# Phase_2.net
KiCad netlist of a schematic drawn in Altium Designer
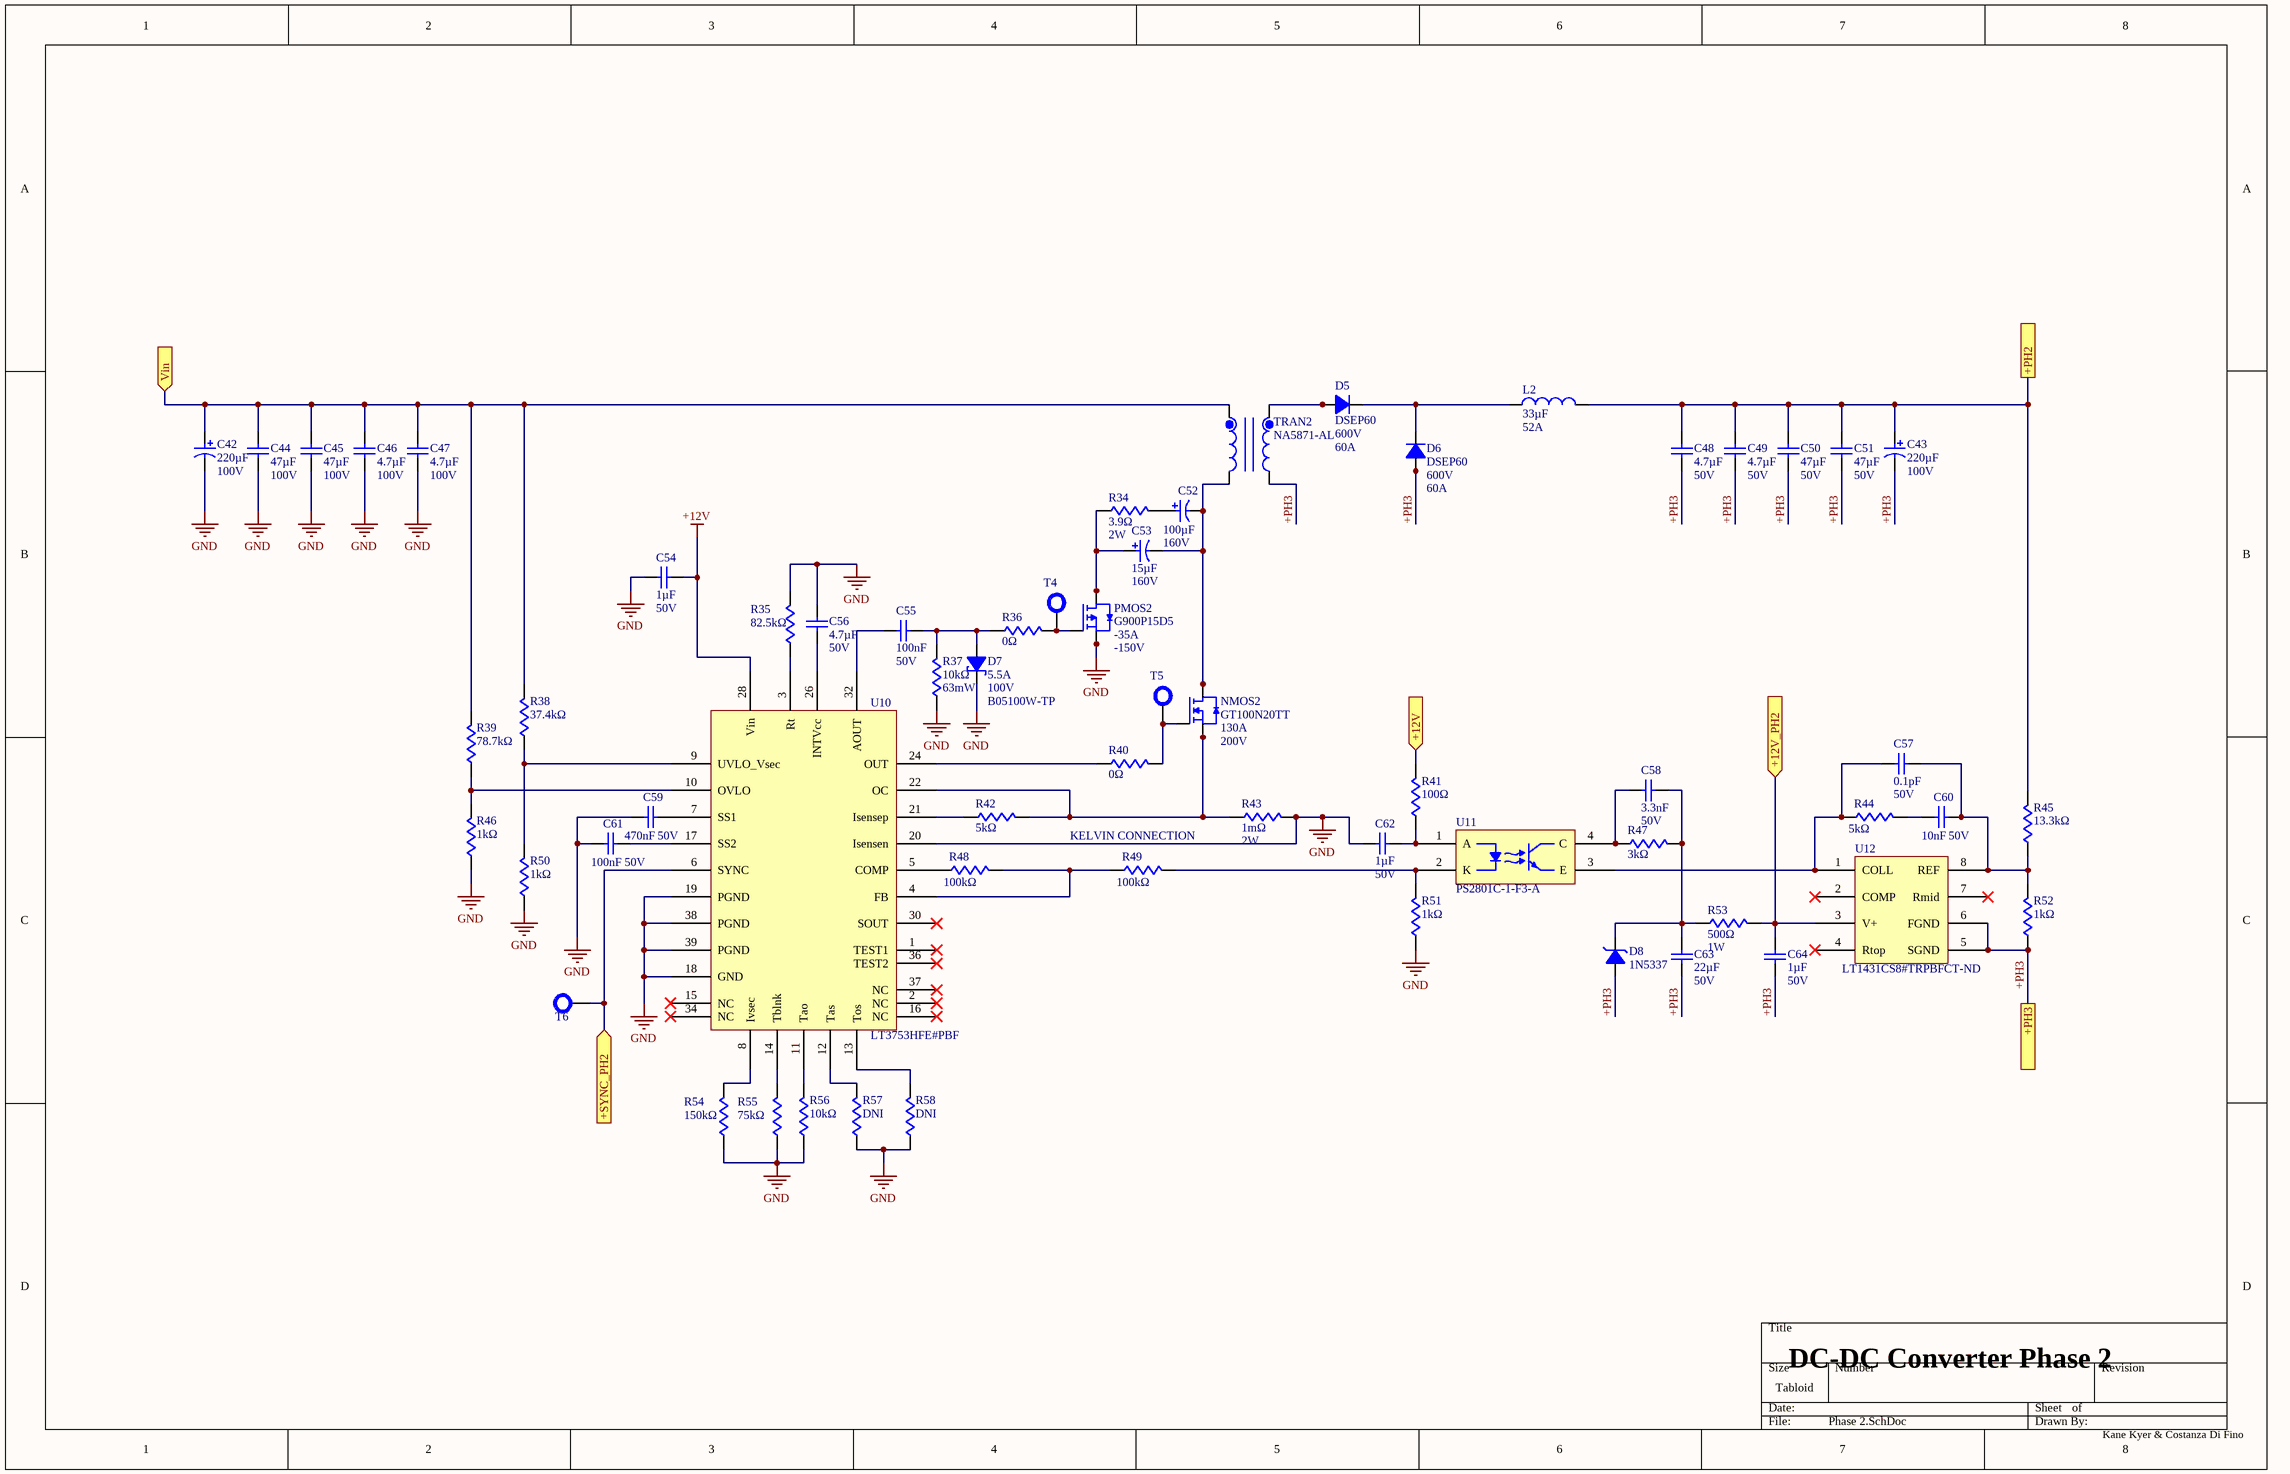
[diagram p0: Phase 2.SchDoc]

(export (version "E")
  (design (tool "Eeschema 10.0.6"))
  (components
    (comp (ref "C42")
      (value "220µF")
      (footprint "C_AEC")
      (description "Radial Can - SMD ALUMINUM ELECTROLYTIC CAPACITOR AFK 100V 220muF ±20% 0.709Dia 18.00mm")
      (fields
        (field (name "MANUFACTURER") "Cornell Dubilier")
        (field (name "MANUFACTURER PART NUMBER") "AFK227M2AR44T-F")
        (field (name "VOLTAGE RATING") "100V")
      )
      (libsource (lib "library") (part "AFK227M2AR44T-F"))
    )
    (comp (ref "C43")
      (value "220µF")
      (footprint "C_AEC")
      (description "Radial Can - SMD ALUMINUM ELECTROLYTIC CAPACITOR AFK 100V 220muF ±20% 0.709Dia 18.00mm")
      (fields
        (field (name "MANUFACTURER") "Cornell Dubilier")
        (field (name "MANUFACTURER PART NUMBER") "AFK227M2AR44T-F")
        (field (name "VOLTAGE RATING") "100V")
      )
      (libsource (lib "library") (part "AFK227M2AR44T-F"))
    )
    (comp (ref "C44")
      (value "47µF")
      (footprint "C_CAA573")
      (description "Multilayer Ceramic Chip Capacitors, Capacitance=47μF, LxWxT: 6.0x7.5x6.4mm")
      (fields
        (field (name "MANUFACTURER") "TDK")
        (field (name "MANUFACTURER PART NUMBER") "CAA573X7S2A476M640LH")
        (field (name "VOLTAGE RATING") "100V")
      )
      (libsource (lib "library") (part "CAA573X7S2A476M640LH"))
    )
    (comp (ref "C45")
      (value "47µF")
      (footprint "C_CAA573")
      (description "Multilayer Ceramic Chip Capacitors, Capacitance=47μF, LxWxT: 6.0x7.5x6.4mm")
      (fields
        (field (name "MANUFACTURER") "TDK")
        (field (name "MANUFACTURER PART NUMBER") "CAA573X7S2A476M640LH")
        (field (name "VOLTAGE RATING") "100V")
      )
      (libsource (lib "library") (part "CAA573X7S2A476M640LH"))
    )
    (comp (ref "C46")
      (value "4.7µF")
      (footprint "C_1210")
      (fields
        (field (name "MANUFACTURER") "Cal-Chip Electronics")
        (field (name "MANUFACTURER PART NUMBER") "GMC32X7S475K100NT")
        (field (name "VOLTAGE RATING (DC)") "100V")
      )
      (libsource (lib "library") (part "GMC32X7S475K100NT"))
    )
    (comp (ref "C47")
      (value "4.7µF")
      (footprint "C_1210")
      (fields
        (field (name "MANUFACTURER") "Cal-Chip Electronics")
        (field (name "MANUFACTURER PART NUMBER") "GMC32X7S475K100NT")
        (field (name "VOLTAGE RATING (DC)") "100V")
      )
      (libsource (lib "library") (part "GMC32X7S475K100NT"))
    )
    (comp (ref "C48")
      (value "4.7µF")
      (footprint "C_1206")
      (fields
        (field (name "MANUFACTURER") "Cal-Chip Electronics")
        (field (name "MANUFACTURER PART NUMBER") "GMC31X7R475K50NT")
        (field (name "VOLTAGE RATING (DC)") "50V")
      )
      (libsource (lib "library") (part "GMC31X7R475K50NT"))
    )
    (comp (ref "C49")
      (value "4.7µF")
      (footprint "C_1206")
      (fields
        (field (name "MANUFACTURER") "Cal-Chip Electronics")
        (field (name "MANUFACTURER PART NUMBER") "GMC31X7R475K50NT")
        (field (name "VOLTAGE RATING (DC)") "50V")
      )
      (libsource (lib "library") (part "GMC31X7R475K50NT"))
    )
    (comp (ref "C50")
      (value "47µF")
      (footprint "C_CKG57N")
      (fields
        (field (name "MANUFACTURER") "TDK")
        (field (name "MANUFACTURER PART NUMBER") "CKG57NX7R1H476M500JJ")
        (field (name "VOLTAGE RATING (DC)") "50V")
      )
      (libsource (lib "library") (part "CKG57NX7R1H476M500JJ"))
    )
    (comp (ref "C51")
      (value "47µF")
      (footprint "C_CKG57N")
      (fields
        (field (name "MANUFACTURER") "TDK")
        (field (name "MANUFACTURER PART NUMBER") "CKG57NX7R1H476M500JJ")
        (field (name "VOLTAGE RATING (DC)") "50V")
      )
      (libsource (lib "library") (part "CKG57NX7R1H476M500JJ"))
    )
    (comp (ref "C52")
      (value "100µF")
      (footprint "UUJ2C101MNJ1MS")
      (description "Aluminum Electrolytic Capacitors 100 F 160 V Radial, SMD 5000 Hrs 105C")
      (fields
        (field (name "MANUFACTURER") "Nichicon")
        (field (name "MANUFACTURER PART NUMBER") "UUJ2C101MNJ1MS")
        (field (name "VOLTAGE RATING (DC)") "160V")
      )
      (libsource (lib "library") (part "UUJ2C101MNJ1MS"))
    )
    (comp (ref "C53")
      (value "15µF")
      (footprint "ULT2C150MNL1GS")
      (description "Radial Can - SMD ALUMINUM ELECTROLYTIC CAPACITOR ULT 160V 15muF ±20% 0.315Dia 8.00mm")
      (fields
        (field (name "MANUFACTURER") "Nichicon")
        (field (name "MANUFACTURER PART NUMBER") "ULT2C150MNL1GS")
        (field (name "VOLTAGE") "160V")
      )
      (libsource (lib "library") (part "ULT2C150MNL1GS"))
    )
    (comp (ref "C54")
      (value "1µF")
      (footprint "C_0805")
      (description "50V 1uF X7R ±10% 0805 Multilayer Ceramic Capacitors MLCC - SMD/SMT ROHS")
      (fields
        (field (name "MANUFACTURER") "Samsung Electro-Mechanics")
        (field (name "MANUFACTURER PART NUMBER") "CL21B105KBFNNNE")
        (field (name "VOLTAGE") "50V")
      )
      (libsource (lib "library") (part "CL21B105KBFNNNE"))
    )
    (comp (ref "C55")
      (value "100nF")
      (footprint "C_0603")
      (description "50V 100nF X7R ±10% 0603 Multilayer Ceramic Capacitors MLCC - SMD/SMT ROHS")
      (fields
        (field (name "MANUFACTURER") "KEMET")
        (field (name "MANUFACTURER PART NUMBER") "C0603C104K5RACTU")
        (field (name "VOLTAGE RATING") "50V")
      )
      (libsource (lib "library") (part "C0603C104K5RACTU"))
    )
    (comp (ref "C56")
      (value "4.7µF")
      (footprint "C_1206")
      (fields
        (field (name "MANUFACTURER") "Cal-Chip Electronics")
        (field (name "MANUFACTURER PART NUMBER") "GMC31X7R475K50NT")
        (field (name "VOLTAGE RATING (DC)") "50V")
      )
      (libsource (lib "library") (part "GMC31X7R475K50NT"))
    )
    (comp (ref "C57")
      (value "0.1pF")
      (footprint "C_0402")
      (description "Multilayer Ceramic Capacitor, 0.1 pF, 50 V, ± 0.05pF, C0G (NP0), 0402 [1005 Metric]")
      (fields
        (field (name "MANUFACTURER") "Murata")
        (field (name "MANUFACTURER PART NUMBER") "GJM1555C1HR10WB01D")
        (field (name "VOLTAGE RATING") "50V")
      )
      (libsource (lib "library") (part "GJM1555C1HR10WB01D"))
    )
    (comp (ref "C58")
      (value "3.3nF")
      (footprint "C_0603")
      (description "50V 3.3nF C0G ±1% 0603 Multilayer Ceramic Capacitors MLCC - SMD/SMT ROHS")
      (fields
        (field (name "MANUFACTURER") "Murata")
        (field (name "MANUFACTURER PART NUMBER") "GCM1885C1H332FA16D")
        (field (name "VOLTAGE RATING") "50V")
      )
      (libsource (lib "library") (part "GCM1885C1H332FA16D"))
    )
    (comp (ref "C59")
      (value "470nF")
      (footprint "C_0402")
      (description "50V 470nF X5R ±10% 0402 Multilayer Ceramic Capacitors MLCC - SMD/SMT ROHS")
      (fields
        (field (name "MANUFACTURER") "Murata")
        (field (name "MANUFACTURER PART NUMBER") "GRM155R61H474KE11D")
        (field (name "VOLTAGE RATING") "50V")
      )
      (libsource (lib "library") (part "GRM155R61H474KE11D"))
    )
    (comp (ref "C60")
      (value "10nF")
      (footprint "C_0603")
      (description "Capacitor, Multilayer, Ceramic, 50V, 10%, X7R, 15% Tc, 0.01Uf, Surface Mount, 0603")
      (fields
        (field (name "MANUFACTURER") "KEMET")
        (field (name "MANUFACTURER PART NUMBER") "C0603C103K5RACTU")
        (field (name "VOLTAGE RATING") "50V")
      )
      (libsource (lib "library") (part "C0603C103K5RACTU"))
    )
    (comp (ref "C61")
      (value "100nF")
      (footprint "C_0603")
      (description "50V 100nF X7R ±10% 0603 Multilayer Ceramic Capacitors MLCC - SMD/SMT ROHS")
      (fields
        (field (name "MANUFACTURER") "KEMET")
        (field (name "MANUFACTURER PART NUMBER") "C0603C104K5RACTU")
        (field (name "VOLTAGE RATING") "50V")
      )
      (libsource (lib "library") (part "C0603C104K5RACTU"))
    )
    (comp (ref "C62")
      (value "1µF")
      (footprint "C_0805")
      (description "50V 1uF X7R ±10% 0805 Multilayer Ceramic Capacitors MLCC - SMD/SMT ROHS")
      (fields
        (field (name "MANUFACTURER") "Samsung Electro-Mechanics")
        (field (name "MANUFACTURER PART NUMBER") "CL21B105KBFNNNE")
        (field (name "VOLTAGE") "50V")
      )
      (libsource (lib "library") (part "CL21B105KBFNNNE"))
    )
    (comp (ref "C63")
      (value "22µF")
      (footprint "C_2220")
      (fields
        (field (name "MANUFACTURER") "Cal-Chip Electronics")
        (field (name "MANUFACTURER PART NUMBER") "GMC55X7R226M50NT")
        (field (name "VOLTAGE RATING (DC)") "50V")
      )
      (libsource (lib "library") (part "GMC55X7R226M50NT"))
    )
    (comp (ref "C64")
      (value "1µF")
      (footprint "C_0805")
      (description "50V 1uF X7R ±10% 0805 Multilayer Ceramic Capacitors MLCC - SMD/SMT ROHS")
      (fields
        (field (name "MANUFACTURER") "Samsung Electro-Mechanics")
        (field (name "MANUFACTURER PART NUMBER") "CL21B105KBFNNNE")
        (field (name "VOLTAGE") "50V")
      )
      (libsource (lib "library") (part "CL21B105KBFNNNE"))
    )
    (comp (ref "D5")
      (value "DSEP60")
      (footprint "D_DSEP60")
      (description "Power Diode Discretes-FRED TO-")
      (fields
        (field (name "MANUFACTURER") "IXYS")
        (field (name "MANUFACTURER PART NUMBER") "DSEP60-06AZ-TRL")
        (field (name "VR") "600V")
        (field (name "IO") "60A")
      )
      (libsource (lib "library") (part "DSEP60-06AZ-TRL"))
    )
    (comp (ref "D6")
      (value "DSEP60")
      (footprint "D_DSEP60")
      (description "Power Diode Discretes-FRED TO-")
      (fields
        (field (name "MANUFACTURER") "IXYS")
        (field (name "MANUFACTURER PART NUMBER") "DSEP60-06AZ-TRL")
        (field (name "VR") "600V")
        (field (name "IO") "60A")
      )
      (libsource (lib "library") (part "DSEP60-06AZ-TRL"))
    )
    (comp (ref "D7")
      (value "B05100W-TP")
      (footprint "D_B05100W")
      (description "Rectifier Diode, Schottky, 1 Phase, 1 Element, 0.5A, 100V V(RRM), Silicon")
      (fields
        (field (name "MANUFACTURER") "MCC")
        (field (name "MAX FORWARD SURGE CURRENT (IFSM)") "5.5A")
        (field (name "MIN BREAKDOWN VOLTAGE") "100V")
        (field (name "MANUFACTURER PART NUMBER") "B05100W-TP")
      )
      (libsource (lib "library") (part "B05100W-TP"))
    )
    (comp (ref "D8")
      (value "1N5337BRLG")
      (footprint "D_1N5337")
      (description "Zener Diode Single 4.7V 5% 2Ohm 5000mW 2-Pin Case 017AA-01 T/R / DIODE ZENER 4.7V 5W AXIAL")
      (fields
        (field (name "MANUFACTURER") "onsemi")
        (field (name "TOLERANCE") "5%")
        (field (name "SUPPLIER PART NUMBER") "1N5337")
      )
      (libsource (lib "library") (part "1N5337BRLG"))
    )
    (comp (ref "L2")
      (value "33µF")
      (footprint "CPEX4141L-330MC")
      (description "Fixed Ind 33UH 52A 1.88 Mohm Th")
      (fields
        (field (name "MANUFACTURER") "Codaca")
        (field (name "MANUFACTURER PART NUMBER") "CPEX4141L-330MC")
        (field (name "IRMS") "52A")
      )
      (libsource (lib "library") (part "CPEX4141L-330MC"))
    )
    (comp (ref "NMOS2")
      (value "GT100N20TT")
      (footprint "GT100N20TT")
      (description "Mosfet N-ch 200V 130A 280W Tolt")
      (fields
        (field (name "MANUFACTURER") "GoFord")
        (field (name "MANUFACTURER PART NUMBER") "GT100N20TT")
        (field (name "ID") "130A")
        (field (name "VDS") "200V")
      )
      (libsource (lib "library") (part "GT100N20TT"))
    )
    (comp (ref "PMOS2")
      (value "G900P15D5")
      (footprint "G900P15")
      (description "P-150V, -60A, RD(max) Less Than 80mOhm at -10V, VTH -1V to -4V, DFN5x6-8L")
      (fields
        (field (name "MANUFACTURER") "GoFord")
        (field (name "MANUFACTURER PART NUMBER") "G900P15D5")
        (field (name "ID") "-35A")
        (field (name "VDS") "-150V")
      )
      (libsource (lib "library") (part "G900P15D5"))
    )
    (comp (ref "R34")
      (value "3.9Ω")
      (footprint "R_SM2W")
      (description "SM Series 3.9 Ohm ±5 % 2 W ±200 ppm/°C Surface Mount Wirewound Resistor")
      (fields
        (field (name "MANUFACTURER") "TE Connectivity")
        (field (name "MANUFACTURER PART NUMBER") "SMW23R9JT")
        (field (name "POWER RATING") "2W")
      )
      (libsource (lib "library") (part "SMW23R9JT"))
    )
    (comp (ref "R35")
      (value "82.5kΩ")
      (footprint "R_0805")
      (description "Res Thick Film 0805 82.5K Ohm 1% 1/8W ±100ppm/°C Molded SMD SMD Paper T/R")
      (fields
        (field (name "MANUFACTURER") "Stackpole Electronics")
        (field (name "MANUFACTURER PART NUMBER") "RMCF0805FT82K5")
      )
      (libsource (lib "library") (part "RMCF0805FT82K5"))
    )
    (comp (ref "R36")
      (value "0Ω")
      (footprint "R_0805")
      (description "Zero Ohm Resistor, Jumper, 0805 [2012 Metric], Thick Film, 125 mW, 2.5 A, Surface Mount Device")
      (fields
        (field (name "MANUFACTURER") "Vishay")
        (field (name "MANUFACTURER PART NUMBER") "CRCW08050000Z0EA")
      )
      (libsource (lib "library") (part "CRCW08050000Z0EA"))
    )
    (comp (ref "R37")
      (value "10kΩ")
      (footprint "R_0402")
      (description "Fixed Resistor, Metal Glaze/thick Film, 0.0625W, 10000ohm, 50V, 1% +/-Tol, Surface Mount, 0402")
      (fields
        (field (name "MANUFACTURER") "Cal-Chip Electronics")
        (field (name "MANUFACTURER PART NUMBER") "RM04F1002CT")
        (field (name "POWER RATING") "63mW")
      )
      (libsource (lib "library") (part "RM04F1002CT"))
    )
    (comp (ref "R38")
      (value "37.4kΩ")
      (footprint "R_0603")
      (description "100mW Thick Film Resistors 75V ±100ppm/℃ ±1% 37.4kΩ 0603 Chip Resistor - Surface Mount ROHS")
      (fields
        (field (name "MANUFACTURER") "Yageo Group")
        (field (name "MANUFACTURER PART NUMBER") "RC0603FR-0737K4L")
      )
      (libsource (lib "library") (part "RC0603FR-0737K4L"))
    )
    (comp (ref "R39")
      (value "78.7kΩ")
      (footprint "R_0603")
      (description "Res Thick Film 0603 78.7K Ohm 1% 0.1W(1/10W) ±100ppm/C Pad SMD T/R")
      (fields
        (field (name "MANUFACTURER") "Yageo Group")
        (field (name "MANUFACTURER PART NUMBER") "RC0603FR-0778K7L")
      )
      (libsource (lib "library") (part "RC0603FR-0778K7L"))
    )
    (comp (ref "R40")
      (value "0Ω")
      (footprint "R_0805")
      (description "Zero Ohm Resistor, Jumper, 0805 [2012 Metric], Thick Film, 125 mW, 2.5 A, Surface Mount Device")
      (fields
        (field (name "MANUFACTURER") "Vishay")
        (field (name "MANUFACTURER PART NUMBER") "CRCW08050000Z0EA")
      )
      (libsource (lib "library") (part "CRCW08050000Z0EA"))
    )
    (comp (ref "R41")
      (value "100Ω")
      (footprint "R_0603")
      (description "Yageo RC0603FR-07100RL 0603 SMD Resistor 100 Ohm thin film chip resistor")
      (fields
        (field (name "MANUFACTURER") "Yageo Group")
        (field (name "MANUFACTURER PART NUMBER") "RC0603FR-07100RL")
      )
      (libsource (lib "library") (part "RC0603FR-07100RL"))
    )
    (comp (ref "R42")
      (value "5kΩ")
      (footprint "R_0402")
      (description "Res Thin Film 0402 5K Ohm 0.1% 0.05W(1/20W) +/-25ppm/C Sulfur Resistant Pad SMD Medical T/R")
      (fields
        (field (name "MANUFACTURER") "Vishay")
        (field (name "MANUFACTURER PART NUMBER") "PNM0402E5001BST1")
      )
      (libsource (lib "library") (part "PNM0402E5001BST1"))
    )
    (comp (ref "R43")
      (value "1mΩ")
      (footprint "R_2512")
      (description "Res Thick Film 2512 1m Ohm 1% 2W ±75ppm/°C Molded SMD Embossed T/R")
      (fields
        (field (name "MANUFACTURER") "Bourns")
        (field (name "MANUFACTURER PART NUMBER") "CRE2512-FZ-R001E-2")
        (field (name "POWER RATING") "2W")
      )
      (libsource (lib "library") (part "CRE2512-FZ-R001E-2"))
    )
    (comp (ref "R44")
      (value "5kΩ")
      (footprint "R_0402")
      (description "Res Thin Film 0402 5K Ohm 0.1% 0.05W(1/20W) +/-25ppm/C Sulfur Resistant Pad SMD Medical T/R")
      (fields
        (field (name "MANUFACTURER") "Vishay")
        (field (name "MANUFACTURER PART NUMBER") "PNM0402E5001BST1")
      )
      (libsource (lib "library") (part "PNM0402E5001BST1"))
    )
    (comp (ref "R45")
      (value "13.3kΩ")
      (footprint "R_0603")
      (description "Res Thick Film 0603 13.3K Ohm 1% 0.1W(1/10W) ±100ppm/C Pad SMD Automotive T/R")
      (fields
        (field (name "MANUFACTURER") "Stackpole Electronics")
        (field (name "MANUFACTURER PART NUMBER") "RMCF0603FT13K3")
      )
      (libsource (lib "library") (part "RMCF0603FT13K3"))
    )
    (comp (ref "R46")
      (value "1kΩ")
      (footprint "R_0402")
      (description "62.5mW Thick Film Resistors ±100ppm/℃ ±1% 1kΩ 0402 Chip Resistor - Surface Mount ROHS")
      (fields
        (field (name "MANUFACTURER") "Cal-Chip Electronics")
        (field (name "MANUFACTURER PART NUMBER") "RM04F1001CT")
      )
      (libsource (lib "library") (part "RM04F1001CT"))
    )
    (comp (ref "R47")
      (value "3kΩ")
      (footprint "C_0402")
      (description "Res Thick Film 0402 3K Ohm 1% 0.063W(1/16W) ±100ppm/C Pad SMD Automotive T/R")
      (fields
        (field (name "MANUFACTURER") "Yageo Group")
        (field (name "MANUFACTURER PART NUMBER") "AC0402FR-073KL")
      )
      (libsource (lib "library") (part "AC0402FR-073KL"))
    )
    (comp (ref "R48")
      (value "100kΩ")
      (footprint "R_0402")
      (description "Fixed Resistor, Metal Glaze/thick Film, 0.0625W, 100000ohm, 50V, 1% +/-Tol, Surface Mount, 0402")
      (fields
        (field (name "MANUFACTURER") "Cal-Chip Electronics")
        (field (name "MANUFACTURER PART NUMBER") "RM04F1003CT")
      )
      (libsource (lib "library") (part "RM04F1003CT"))
    )
    (comp (ref "R49")
      (value "100kΩ")
      (footprint "R_0402")
      (description "Fixed Resistor, Metal Glaze/thick Film, 0.0625W, 100000ohm, 50V, 1% +/-Tol, Surface Mount, 0402")
      (fields
        (field (name "MANUFACTURER") "Cal-Chip Electronics")
        (field (name "MANUFACTURER PART NUMBER") "RM04F1003CT")
      )
      (libsource (lib "library") (part "RM04F1003CT"))
    )
    (comp (ref "R50")
      (value "1kΩ")
      (footprint "R_0402")
      (description "62.5mW Thick Film Resistors ±100ppm/℃ ±1% 1kΩ 0402 Chip Resistor - Surface Mount ROHS")
      (fields
        (field (name "MANUFACTURER") "Cal-Chip Electronics")
        (field (name "MANUFACTURER PART NUMBER") "RM04F1001CT")
      )
      (libsource (lib "library") (part "RM04F1001CT"))
    )
    (comp (ref "R51")
      (value "1kΩ")
      (footprint "R_0402")
      (description "62.5mW Thick Film Resistors ±100ppm/℃ ±1% 1kΩ 0402 Chip Resistor - Surface Mount ROHS")
      (fields
        (field (name "MANUFACTURER") "Cal-Chip Electronics")
        (field (name "MANUFACTURER PART NUMBER") "RM04F1001CT")
      )
      (libsource (lib "library") (part "RM04F1001CT"))
    )
    (comp (ref "R52")
      (value "1kΩ")
      (footprint "R_0402")
      (description "62.5mW Thick Film Resistors ±100ppm/℃ ±1% 1kΩ 0402 Chip Resistor - Surface Mount ROHS")
      (fields
        (field (name "MANUFACTURER") "Cal-Chip Electronics")
        (field (name "MANUFACTURER PART NUMBER") "RM04F1001CT")
      )
      (libsource (lib "library") (part "RM04F1001CT"))
    )
    (comp (ref "R53")
      (value "500Ω")
      (footprint "R_WSC2515")
      (description "Fixed Resistor, Wire Wound, 1W, 500ohm, 22.3607V, 1% +/-Tol, 20ppm/Cel, Surface Mount, 2515")
      (fields
        (field (name "MANUFACTURER") "Vishay")
        (field (name "MANUFACTURER PART NUMBER") "WSC2515500R0FEB")
        (field (name "POWER RATING") "1W")
      )
      (libsource (lib "library") (part "WSC2515500R0FEB"))
    )
    (comp (ref "R54")
      (value "150kΩ")
      (footprint "R_0603")
      (description "100mW Thick Film Resistors 75V ±100ppm/℃ ±1% 150kΩ 0603 Chip Resistor - Surface Mount ROHS")
      (fields
        (field (name "MANUFACTURER") "Yageo Group")
        (field (name "MANUFACTURER PART NUMBER") "RC0603FR-07150KL")
      )
      (libsource (lib "library") (part "RC0603FR-07150KL"))
    )
    (comp (ref "R55")
      (value "75kΩ")
      (footprint "R_0603")
      (description "Res Thick Film 0603 75K Ohm 1% 0.1W(1/10W) ±100ppm/C Pad SMD T/R Automotive AEC-Q200")
      (fields
        (field (name "MANUFACTURER") "Yageo Group")
        (field (name "MANUFACTURER PART NUMBER") "AC0603FR-0775KL")
      )
      (libsource (lib "library") (part "AC0603FR-0775KL"))
    )
    (comp (ref "R56")
      (value "10kΩ")
      (footprint "R_0402")
      (description "Fixed Resistor, Metal Glaze/thick Film, 0.0625W, 10000ohm, 50V, 1% +/-Tol, Surface Mount, 0402")
      (fields
        (field (name "MANUFACTURER") "Cal-Chip Electronics")
        (field (name "MANUFACTURER PART NUMBER") "RM04F1002CT")
      )
      (libsource (lib "library") (part "RM04F1002CT"))
    )
    (comp (ref "R57")
      (value "DNI")
      (footprint "R_0805")
      (description "Zero Ohm Resistor, Jumper, 0805 [2012 Metric], Thick Film, 125 mW, 2.5 A, Surface Mount Device")
      (fields
        (field (name "MANUFACTURER") "Vishay")
        (field (name "MANUFACTURER PART NUMBER") "CRCW08050000Z0EA")
      )
      (libsource (lib "library") (part "CRCW08050000Z0EA"))
    )
    (comp (ref "R58")
      (value "DNI")
      (footprint "R_0805")
      (description "Zero Ohm Resistor, Jumper, 0805 [2012 Metric], Thick Film, 125 mW, 2.5 A, Surface Mount Device")
      (fields
        (field (name "MANUFACTURER") "Vishay")
        (field (name "MANUFACTURER PART NUMBER") "CRCW08050000Z0EA")
      )
      (libsource (lib "library") (part "CRCW08050000Z0EA"))
    )
    (comp (ref "T4") (value "TEST") (footprint "TEST_POINT") (libsource (lib "library") (part "TEST")))
    (comp (ref "T5") (value "TEST") (footprint "TEST_POINT") (libsource (lib "library") (part "TEST")))
    (comp (ref "T6") (value "TEST") (footprint "TEST_POINT") (libsource (lib "library") (part "TEST")))
    (comp (ref "TRAN2")
      (value "NA5871-AL")
      (footprint "NA5871-AL")
      (description "Transformer, planar, for TI UCC28950, SMT, RoHS")
      (fields (field (name "MANUFACTURER") "Coilcraft") (field (name "SUPPLIER PART NUMBER") "NA5871-AL"))
      (libsource (lib "library") (part "NA5871-AL"))
    )
    (comp (ref "U10")
      (value "LT3753HFE#PBF")
      (footprint "LT3753")
      (description "500kHz 8.5V~100V Buck-boost type 1 TSSOP-38-EP-4.4mm DC-DC Controllers ROHS")
      (fields
        (field (name "MANUFACTURER") "Analog Devices")
        (field (name "MANUFACTURER PART NUMBER") "LT3753HFE#PBF")
      )
      (libsource (lib "library") (part "LT3753HFE#PBF"))
    )
    (comp (ref "U11")
      (value "PS2801C-1-F3-A")
      (footprint "PS2801C")
      (description "Optocoupler DC-IN 1-CH Transistor DC-OUT 4-Pin SSOP T/R")
      (fields
        (field (name "MANUFACTURER") "Renesas")
        (field (name "MANUFACTURER PART NUMBER") "PS2801C-1-F3-A")
      )
      (libsource (lib "library") (part "PS2801C-1-F3-A"))
    )
    (comp (ref "U12")
      (value "LT1431CS8#TRPBF")
      (footprint "LT1431")
      (description "V-Ref Adjustable 2.5V to 36V 100mA 8-Pin SOIC N T/R")
      (fields
        (field (name "SUPPLIER PART NUMBER") "LT1431CS8#TRPBFCT-ND")
        (field (name "MANUFACTURER") "Analog Devices")
        (field (name "TOLERANCE") "0.4%")
      )
      (libsource (lib "library") (part "LT1431CS8#TRPBF"))
    )
  )
  (nets
    (net (code "1") (name "+12V") (class "Default")
      (node (ref "C54") (pin "2") (pintype "passive"))
      (node (ref "R41") (pin "2") (pintype "passive"))
      (node (ref "U10") (pin "28") (pinfunction "Vin_28") (pintype "passive"))
    )
    (net (code "2") (name "/+12V_PH2") (class "Default")
      (node (ref "C64") (pin "2") (pintype "passive"))
      (node (ref "R53") (pin "2") (pintype "passive"))
      (node (ref "U12") (pin "3") (pinfunction "V+_3") (pintype "passive"))
    )
    (net (code "3") (name "/+PH2") (class "Default")
      (node (ref "C43") (pin "1") (pintype "passive"))
      (node (ref "C48") (pin "2") (pintype "passive"))
      (node (ref "C49") (pin "2") (pintype "passive"))
      (node (ref "C50") (pin "2") (pintype "passive"))
      (node (ref "C51") (pin "2") (pintype "passive"))
      (node (ref "L2") (pin "2") (pintype "passive"))
      (node (ref "R45") (pin "2") (pintype "passive"))
    )
    (net (code "4") (name "/+PH3") (class "Default")
      (node (ref "C43") (pin "2") (pintype "passive"))
      (node (ref "C48") (pin "1") (pintype "passive"))
      (node (ref "C49") (pin "1") (pintype "passive"))
      (node (ref "C50") (pin "1") (pintype "passive"))
      (node (ref "C51") (pin "1") (pintype "passive"))
      (node (ref "C63") (pin "1") (pintype "passive"))
      (node (ref "C64") (pin "1") (pintype "passive"))
      (node (ref "D6") (pin "1") (pinfunction "A_1") (pintype "passive"))
      (node (ref "D6") (pin "3") (pinfunction "A_3") (pintype "passive"))
      (node (ref "D8") (pin "2") (pintype "passive"))
      (node (ref "R52") (pin "1") (pintype "passive"))
      (node (ref "TRAN2") (pin "11") (pintype "passive"))
      (node (ref "U12") (pin "5") (pinfunction "SGND_5") (pintype "passive"))
      (node (ref "U12") (pin "6") (pinfunction "FGND_6") (pintype "passive"))
    )
    (net (code "5") (name "/+SYNC_PH2") (class "Default")
      (node (ref "T6") (pin "1") (pinfunction "1_1") (pintype "passive"))
      (node (ref "U10") (pin "6") (pinfunction "SYNC_6") (pintype "passive"))
    )
    (net (code "6") (name "/Vin") (class "Default")
      (node (ref "C42") (pin "1") (pintype "passive"))
      (node (ref "C44") (pin "2") (pintype "passive"))
      (node (ref "C45") (pin "2") (pintype "passive"))
      (node (ref "C46") (pin "2") (pintype "passive"))
      (node (ref "C47") (pin "2") (pintype "passive"))
      (node (ref "R38") (pin "2") (pintype "passive"))
      (node (ref "R39") (pin "2") (pintype "passive"))
      (node (ref "TRAN2") (pin "1") (pintype "passive"))
    )
    (net (code "7") (name "GND") (class "Default")
      (node (ref "C42") (pin "2") (pintype "passive"))
      (node (ref "C44") (pin "1") (pintype "passive"))
      (node (ref "C45") (pin "1") (pintype "passive"))
      (node (ref "C46") (pin "1") (pintype "passive"))
      (node (ref "C47") (pin "1") (pintype "passive"))
      (node (ref "C54") (pin "1") (pintype "passive"))
      (node (ref "C56") (pin "1") (pintype "passive"))
      (node (ref "C59") (pin "1") (pintype "passive"))
      (node (ref "C61") (pin "1") (pintype "passive"))
      (node (ref "C62") (pin "1") (pintype "passive"))
      (node (ref "D7") (pin "1") (pintype "passive"))
      (node (ref "PMOS2") (pin "1") (pinfunction "S_1") (pintype "passive"))
      (node (ref "PMOS2") (pin "2") (pinfunction "S_2") (pintype "passive"))
      (node (ref "PMOS2") (pin "3") (pinfunction "S_3") (pintype "passive"))
      (node (ref "R35") (pin "2") (pintype "passive"))
      (node (ref "R37") (pin "1") (pintype "passive"))
      (node (ref "R43") (pin "2") (pintype "passive"))
      (node (ref "R46") (pin "1") (pintype "passive"))
      (node (ref "R50") (pin "1") (pintype "passive"))
      (node (ref "R51") (pin "1") (pintype "passive"))
      (node (ref "R54") (pin "1") (pintype "passive"))
      (node (ref "R55") (pin "1") (pintype "passive"))
      (node (ref "R56") (pin "1") (pintype "passive"))
      (node (ref "R57") (pin "1") (pintype "passive"))
      (node (ref "R58") (pin "1") (pintype "passive"))
      (node (ref "U10") (pin "18") (pinfunction "GND_18") (pintype "passive"))
      (node (ref "U10") (pin "19") (pinfunction "PGND_19") (pintype "passive"))
      (node (ref "U10") (pin "20") (pinfunction "Isensen_20") (pintype "passive"))
      (node (ref "U10") (pin "38") (pinfunction "PGND_38") (pintype "passive"))
      (node (ref "U10") (pin "39") (pinfunction "PGND_39") (pintype "passive"))
    )
    (net (code "8") (name "Net-(C52-Pad1)") (class "Default")
      (node (ref "C52") (pin "1") (pintype "passive"))
      (node (ref "R34") (pin "2") (pintype "passive"))
    )
    (net (code "9") (name "Net-(C52-Pad2)") (class "Default")
      (node (ref "C52") (pin "2") (pintype "passive"))
      (node (ref "C53") (pin "2") (pintype "passive"))
      (node (ref "NMOS2") (pin "10") (pinfunction "D_10") (pintype "passive"))
      (node (ref "NMOS2") (pin "11") (pinfunction "D_11") (pintype "passive"))
      (node (ref "NMOS2") (pin "12") (pinfunction "D_12") (pintype "passive"))
      (node (ref "NMOS2") (pin "13") (pinfunction "D_13") (pintype "passive"))
      (node (ref "NMOS2") (pin "14") (pinfunction "D_14") (pintype "passive"))
      (node (ref "NMOS2") (pin "15") (pinfunction "D_15") (pintype "passive"))
      (node (ref "NMOS2") (pin "16") (pinfunction "D_16") (pintype "passive"))
      (node (ref "NMOS2") (pin "9") (pinfunction "D_9") (pintype "passive"))
      (node (ref "TRAN2") (pin "4") (pintype "passive"))
    )
    (net (code "10") (name "Net-(C53-Pad1)") (class "Default")
      (node (ref "C53") (pin "1") (pintype "passive"))
      (node (ref "PMOS2") (pin "5") (pinfunction "D_5") (pintype "passive"))
      (node (ref "PMOS2") (pin "6") (pinfunction "D_6") (pintype "passive"))
      (node (ref "PMOS2") (pin "7") (pinfunction "D_7") (pintype "passive"))
      (node (ref "PMOS2") (pin "8") (pinfunction "D_8") (pintype "passive"))
      (node (ref "R34") (pin "1") (pintype "passive"))
    )
    (net (code "11") (name "Net-(C55-Pad2)") (class "Default")
      (node (ref "C55") (pin "2") (pintype "passive"))
      (node (ref "D7") (pin "2") (pintype "passive"))
      (node (ref "R36") (pin "1") (pintype "passive"))
      (node (ref "R37") (pin "2") (pintype "passive"))
    )
    (net (code "12") (name "Net-(C58-Pad2)") (class "Default")
      (node (ref "C58") (pin "2") (pintype "passive"))
      (node (ref "C63") (pin "2") (pintype "passive"))
      (node (ref "D8") (pin "1") (pintype "passive"))
      (node (ref "R47") (pin "2") (pintype "passive"))
      (node (ref "R53") (pin "1") (pintype "passive"))
    )
    (net (code "13") (name "Net-(C60-Pad1)") (class "Default")
      (node (ref "C60") (pin "1") (pintype "passive"))
      (node (ref "R44") (pin "2") (pintype "passive"))
    )
    (net (code "14") (name "Net-(D5-A-Pad1)") (class "Default")
      (node (ref "D5") (pin "1") (pinfunction "A_1") (pintype "passive"))
      (node (ref "D5") (pin "3") (pinfunction "A_3") (pintype "passive"))
      (node (ref "TRAN2") (pin "6") (pintype "passive"))
    )
    (net (code "15") (name "Net-(D5-C)") (class "Default")
      (node (ref "D5") (pin "4") (pinfunction "C_4") (pintype "passive"))
      (node (ref "D6") (pin "4") (pinfunction "C_4") (pintype "passive"))
      (node (ref "L2") (pin "1") (pintype "passive"))
    )
    (net (code "16") (name "Net-(NMOS2-G)") (class "Default")
      (node (ref "NMOS2") (pin "8") (pinfunction "G_8") (pintype "passive"))
      (node (ref "R40") (pin "2") (pintype "passive"))
      (node (ref "T5") (pin "1") (pinfunction "1_1") (pintype "passive"))
    )
    (net (code "17") (name "Net-(PMOS2-G)") (class "Default")
      (node (ref "PMOS2") (pin "4") (pinfunction "G_4") (pintype "passive"))
      (node (ref "R36") (pin "2") (pintype "passive"))
      (node (ref "T4") (pin "1") (pinfunction "1_1") (pintype "passive"))
    )
    (net (code "18") (name "Net-(U10-AOUT)") (class "Default")
      (node (ref "C55") (pin "1") (pintype "passive"))
      (node (ref "U10") (pin "32") (pinfunction "AOUT_32") (pintype "passive"))
    )
    (net (code "19") (name "Net-(U10-COMP)") (class "Default")
      (node (ref "R48") (pin "1") (pintype "passive"))
      (node (ref "U10") (pin "5") (pinfunction "COMP_5") (pintype "passive"))
    )
    (net (code "20") (name "Net-(U10-FB)") (class "Default")
      (node (ref "R48") (pin "2") (pintype "passive"))
      (node (ref "R49") (pin "1") (pintype "passive"))
      (node (ref "U10") (pin "4") (pinfunction "FB_4") (pintype "passive"))
    )
    (net (code "21") (name "Net-(U10-INTVcc)") (class "Default")
      (node (ref "C56") (pin "2") (pintype "passive"))
      (node (ref "U10") (pin "26") (pinfunction "INTVcc_26") (pintype "passive"))
    )
    (net (code "22") (name "Net-(U10-Isensep)") (class "Default")
      (node (ref "R42") (pin "1") (pintype "passive"))
      (node (ref "U10") (pin "21") (pinfunction "Isensep_21") (pintype "passive"))
    )
    (net (code "23") (name "Net-(U10-Ivsec)") (class "Default")
      (node (ref "R54") (pin "2") (pintype "passive"))
      (node (ref "U10") (pin "8") (pinfunction "Ivsec_8") (pintype "passive"))
    )
    (net (code "24") (name "Net-(U10-OC)") (class "Default")
      (node (ref "NMOS2") (pin "1") (pinfunction "S_1") (pintype "passive"))
      (node (ref "NMOS2") (pin "2") (pinfunction "S_2") (pintype "passive"))
      (node (ref "NMOS2") (pin "3") (pinfunction "S_3") (pintype "passive"))
      (node (ref "NMOS2") (pin "4") (pinfunction "S_4") (pintype "passive"))
      (node (ref "NMOS2") (pin "5") (pinfunction "S_5") (pintype "passive"))
      (node (ref "NMOS2") (pin "6") (pinfunction "S_6") (pintype "passive"))
      (node (ref "NMOS2") (pin "7") (pinfunction "S_7") (pintype "passive"))
      (node (ref "R42") (pin "2") (pintype "passive"))
      (node (ref "R43") (pin "1") (pintype "passive"))
      (node (ref "U10") (pin "22") (pinfunction "OC_22") (pintype "passive"))
    )
    (net (code "25") (name "Net-(U10-OUT)") (class "Default")
      (node (ref "R40") (pin "1") (pintype "passive"))
      (node (ref "U10") (pin "24") (pinfunction "OUT_24") (pintype "passive"))
    )
    (net (code "26") (name "Net-(U10-OVLO)") (class "Default")
      (node (ref "R39") (pin "1") (pintype "passive"))
      (node (ref "R46") (pin "2") (pintype "passive"))
      (node (ref "U10") (pin "10") (pinfunction "OVLO_10") (pintype "passive"))
    )
    (net (code "27") (name "Net-(U10-Rt)") (class "Default")
      (node (ref "R35") (pin "1") (pintype "passive"))
      (node (ref "U10") (pin "3") (pinfunction "Rt_3") (pintype "passive"))
    )
    (net (code "28") (name "Net-(U10-SS1)") (class "Default")
      (node (ref "C59") (pin "2") (pintype "passive"))
      (node (ref "U10") (pin "7") (pinfunction "SS1_7") (pintype "passive"))
    )
    (net (code "29") (name "Net-(U10-SS2)") (class "Default")
      (node (ref "C61") (pin "2") (pintype "passive"))
      (node (ref "U10") (pin "17") (pinfunction "SS2_17") (pintype "passive"))
    )
    (net (code "30") (name "Net-(U10-Tao)") (class "Default")
      (node (ref "R56") (pin "2") (pintype "passive"))
      (node (ref "U10") (pin "11") (pinfunction "Tao_11") (pintype "passive"))
    )
    (net (code "31") (name "Net-(U10-Tas)") (class "Default")
      (node (ref "R57") (pin "2") (pintype "passive"))
      (node (ref "U10") (pin "12") (pinfunction "Tas_12") (pintype "passive"))
    )
    (net (code "32") (name "Net-(U10-Tblnk)") (class "Default")
      (node (ref "R55") (pin "2") (pintype "passive"))
      (node (ref "U10") (pin "14") (pinfunction "Tblnk_14") (pintype "passive"))
    )
    (net (code "33") (name "Net-(U10-Tos)") (class "Default")
      (node (ref "R58") (pin "2") (pintype "passive"))
      (node (ref "U10") (pin "13") (pinfunction "Tos_13") (pintype "passive"))
    )
    (net (code "34") (name "Net-(U10-UVLO_Vsec)") (class "Default")
      (node (ref "R38") (pin "1") (pintype "passive"))
      (node (ref "R50") (pin "2") (pintype "passive"))
      (node (ref "U10") (pin "9") (pinfunction "UVLO_Vsec_9") (pintype "passive"))
    )
    (net (code "35") (name "Net-(U11-A)") (class "Default")
      (node (ref "C62") (pin "2") (pintype "passive"))
      (node (ref "R41") (pin "1") (pintype "passive"))
      (node (ref "U11") (pin "1") (pinfunction "A_1") (pintype "passive"))
    )
    (net (code "36") (name "Net-(U11-C)") (class "Default")
      (node (ref "C58") (pin "1") (pintype "passive"))
      (node (ref "R47") (pin "1") (pintype "passive"))
      (node (ref "U11") (pin "4") (pinfunction "C_4") (pintype "passive"))
    )
    (net (code "37") (name "Net-(U11-E)") (class "Default")
      (node (ref "C57") (pin "1") (pintype "passive"))
      (node (ref "R44") (pin "1") (pintype "passive"))
      (node (ref "U11") (pin "3") (pinfunction "E_3") (pintype "passive"))
      (node (ref "U12") (pin "1") (pinfunction "COLL_1") (pintype "passive"))
    )
    (net (code "38") (name "Net-(U11-K)") (class "Default")
      (node (ref "R49") (pin "2") (pintype "passive"))
      (node (ref "R51") (pin "2") (pintype "passive"))
      (node (ref "U11") (pin "2") (pinfunction "K_2") (pintype "passive"))
    )
    (net (code "39") (name "Net-(U12-REF)") (class "Default")
      (node (ref "C57") (pin "2") (pintype "passive"))
      (node (ref "C60") (pin "2") (pintype "passive"))
      (node (ref "R45") (pin "1") (pintype "passive"))
      (node (ref "R52") (pin "2") (pintype "passive"))
      (node (ref "U12") (pin "8") (pinfunction "REF_8") (pintype "passive"))
    )
    (net (code "40") (name "unconnected-(U10-NC-Pad2)") (class "Default")
      (node (ref "U10") (pin "2") (pinfunction "NC_2") (pintype "passive+no_connect"))
    )
    (net (code "41") (name "unconnected-(U10-NC-Pad15)") (class "Default")
      (node (ref "U10") (pin "15") (pinfunction "NC_15") (pintype "passive+no_connect"))
    )
    (net (code "42") (name "unconnected-(U10-NC-Pad16)") (class "Default")
      (node (ref "U10") (pin "16") (pinfunction "NC_16") (pintype "passive+no_connect"))
    )
    (net (code "43") (name "unconnected-(U10-NC-Pad34)") (class "Default")
      (node (ref "U10") (pin "34") (pinfunction "NC_34") (pintype "passive+no_connect"))
    )
    (net (code "44") (name "unconnected-(U10-NC-Pad37)") (class "Default")
      (node (ref "U10") (pin "37") (pinfunction "NC_37") (pintype "passive+no_connect"))
    )
    (net (code "45") (name "unconnected-(U10-SOUT-Pad30)") (class "Default")
      (node (ref "U10") (pin "30") (pinfunction "SOUT_30") (pintype "passive+no_connect"))
    )
    (net (code "46") (name "unconnected-(U10-TEST1-Pad1)") (class "Default")
      (node (ref "U10") (pin "1") (pinfunction "TEST1_1") (pintype "passive+no_connect"))
    )
    (net (code "47") (name "unconnected-(U10-TEST2-Pad36)") (class "Default")
      (node (ref "U10") (pin "36") (pinfunction "TEST2_36") (pintype "passive+no_connect"))
    )
    (net (code "48") (name "unconnected-(U12-COMP-Pad2)") (class "Default")
      (node (ref "U12") (pin "2") (pinfunction "COMP_2") (pintype "passive+no_connect"))
    )
    (net (code "49") (name "unconnected-(U12-Rmid-Pad7)") (class "Default")
      (node (ref "U12") (pin "7") (pinfunction "Rmid_7") (pintype "passive+no_connect"))
    )
    (net (code "50") (name "unconnected-(U12-Rtop-Pad4)") (class "Default")
      (node (ref "U12") (pin "4") (pinfunction "Rtop_4") (pintype "passive+no_connect"))
    )
  )
)
